# Sensor_Brushless_Driver_V1_0.net
KiCad netlist of a schematic drawn in Altium Designer
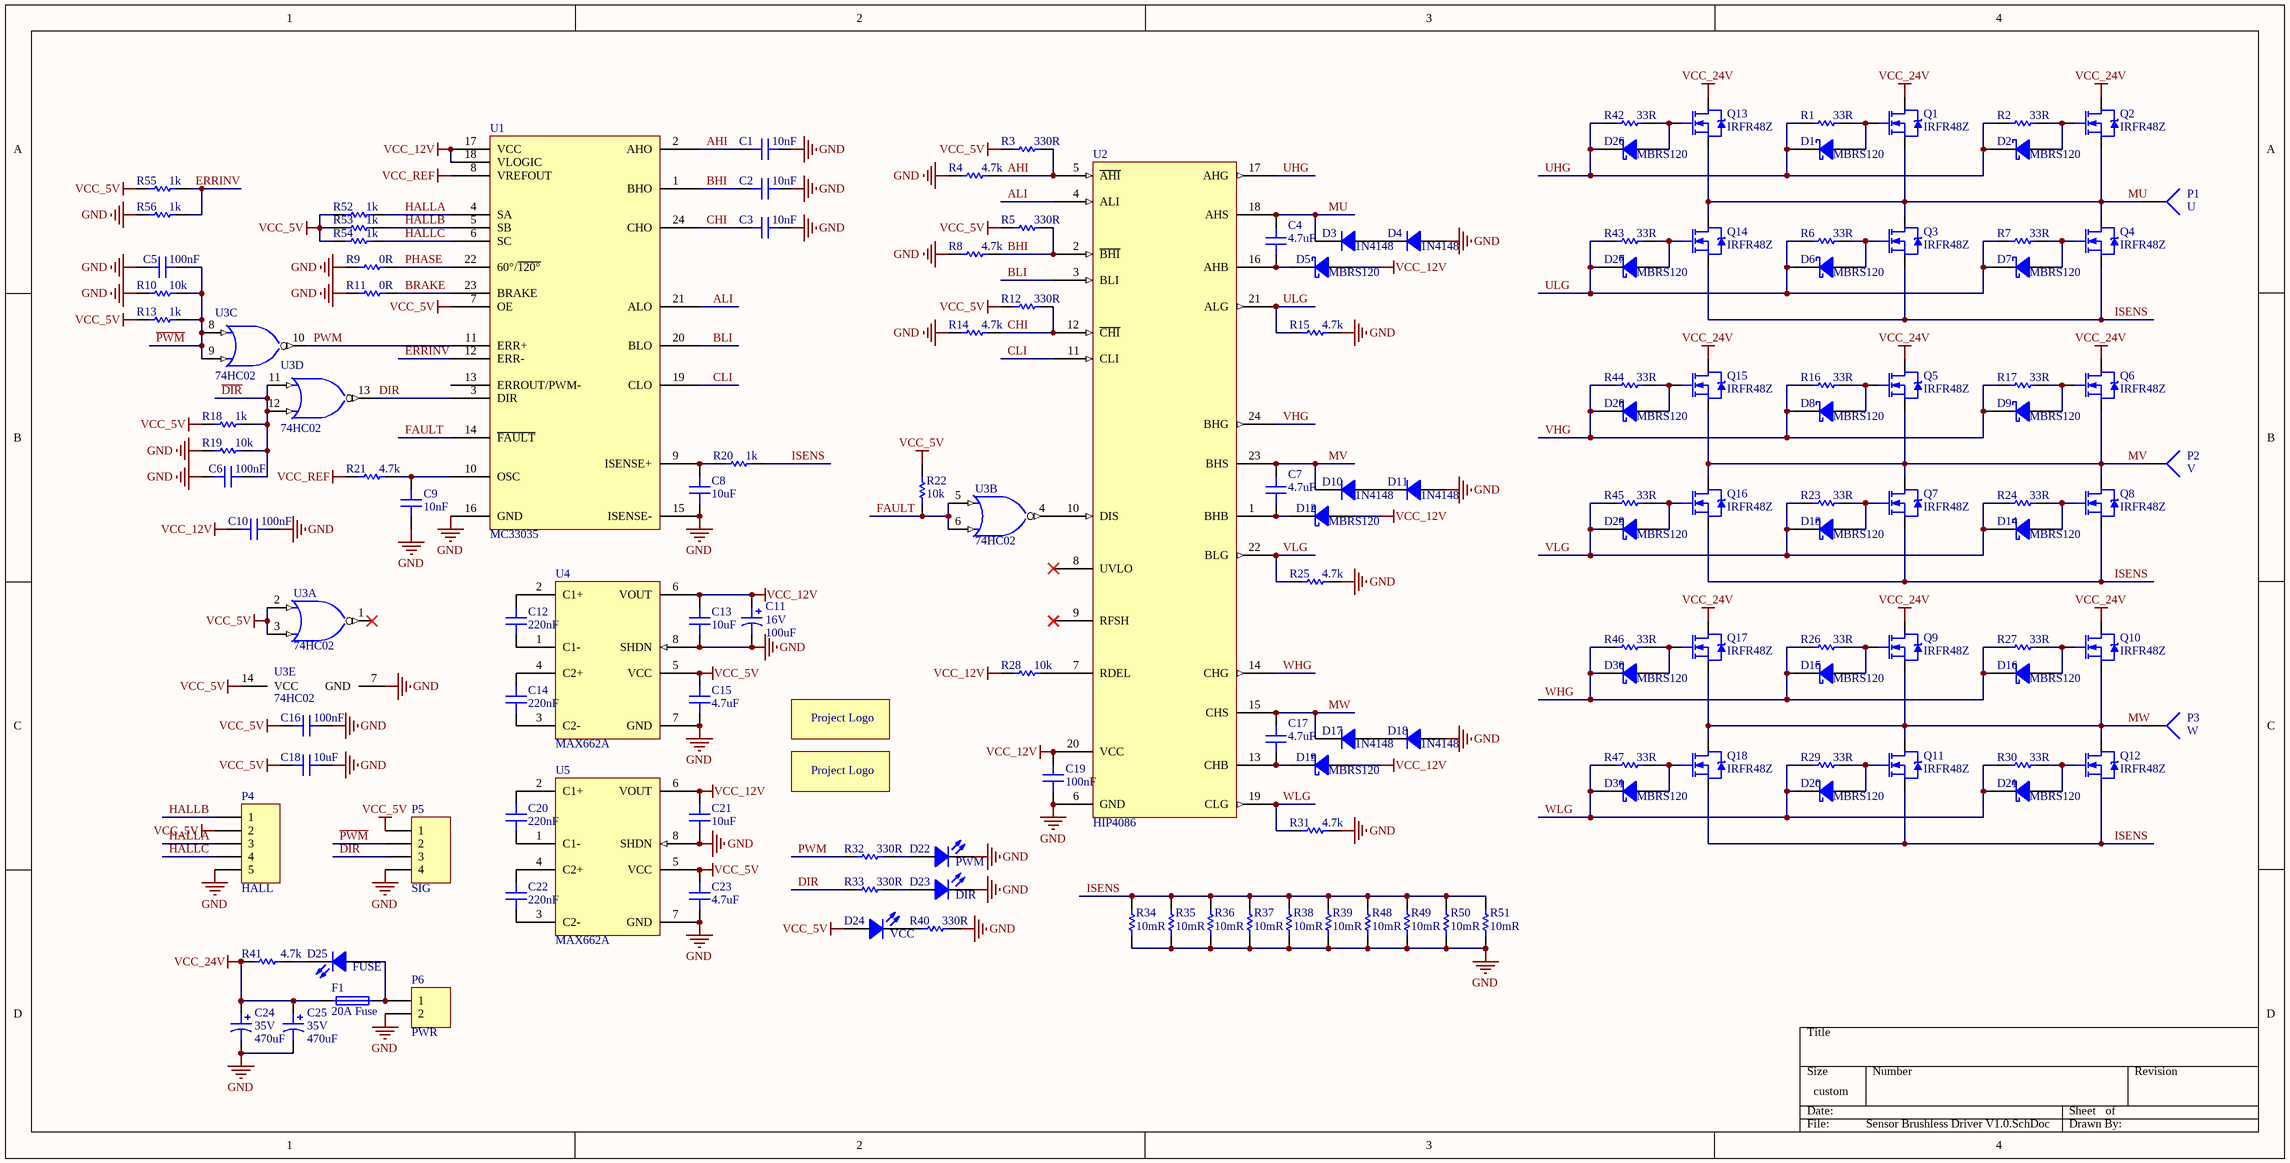
[diagram p0: Sensor Brushless Driver V1.0.SchDoc]

(export (version "E")
  (design (tool "Eeschema 10.0.6"))
  (components
    (comp (ref "C1")
      (value "10nF")
      (footprint "CC2012-0805")
      (description "Capacitor (Semiconductor SIM Model)")
      (libsource (lib "Robocon_RCL") (part "Cap Semi"))
    )
    (comp (ref "C2")
      (value "10nF")
      (footprint "CC2012-0805")
      (description "Capacitor (Semiconductor SIM Model)")
      (libsource (lib "Robocon_RCL") (part "Cap Semi"))
    )
    (comp (ref "C3")
      (value "10nF")
      (footprint "CC2012-0805")
      (description "Capacitor (Semiconductor SIM Model)")
      (libsource (lib "Robocon_RCL") (part "Cap Semi"))
    )
    (comp (ref "C4")
      (value "4.7uF")
      (footprint "CC2012-0805")
      (description "Capacitor (Semiconductor SIM Model)")
      (libsource (lib "Robocon_RCL") (part "Cap Semi"))
    )
    (comp (ref "C5")
      (value "100nF")
      (footprint "CC2012-0805")
      (description "Capacitor (Semiconductor SIM Model)")
      (libsource (lib "Robocon_RCL") (part "Cap Semi"))
    )
    (comp (ref "C6")
      (value "100nF")
      (footprint "CC2012-0805")
      (description "Capacitor (Semiconductor SIM Model)")
      (libsource (lib "Robocon_RCL") (part "Cap Semi"))
    )
    (comp (ref "C7")
      (value "4.7uF")
      (footprint "CC2012-0805")
      (description "Capacitor (Semiconductor SIM Model)")
      (libsource (lib "Robocon_RCL") (part "Cap Semi"))
    )
    (comp (ref "C8")
      (value "10uF")
      (footprint "CC3216-1206")
      (description "Capacitor (Semiconductor SIM Model)")
      (libsource (lib "Robocon_RCL") (part "Cap Semi"))
    )
    (comp (ref "C9")
      (value "10nF")
      (footprint "CC2012-0805")
      (description "Capacitor (Semiconductor SIM Model)")
      (libsource (lib "Robocon_RCL") (part "Cap Semi"))
    )
    (comp (ref "C10")
      (value "100nF")
      (footprint "CC2012-0805")
      (description "Capacitor (Semiconductor SIM Model)")
      (libsource (lib "Robocon_RCL") (part "Cap Semi"))
    )
    (comp (ref "C11")
      (value "100uF")
      (footprint "EIA7343")
      (description "Polarized Capacitor (Axial)")
      (fields (field (name "VOLTAGE") "16V"))
      (libsource (lib "Robocon_RCL") (part "Cap Pol SMD"))
    )
    (comp (ref "C12")
      (value "220nF")
      (footprint "CC2012-0805")
      (description "Capacitor (Semiconductor SIM Model)")
      (libsource (lib "Robocon_RCL") (part "Cap Semi"))
    )
    (comp (ref "C13")
      (value "10uF")
      (footprint "CC3216-1206")
      (description "Capacitor (Semiconductor SIM Model)")
      (libsource (lib "Robocon_RCL") (part "Cap Semi"))
    )
    (comp (ref "C14")
      (value "220nF")
      (footprint "CC2012-0805")
      (description "Capacitor (Semiconductor SIM Model)")
      (libsource (lib "Robocon_RCL") (part "Cap Semi"))
    )
    (comp (ref "C15")
      (value "4.7uF")
      (footprint "CC2012-0805")
      (description "Capacitor (Semiconductor SIM Model)")
      (libsource (lib "Robocon_RCL") (part "Cap Semi"))
    )
    (comp (ref "C16")
      (value "100nF")
      (footprint "CC2012-0805")
      (description "Capacitor (Semiconductor SIM Model)")
      (libsource (lib "Robocon_RCL") (part "Cap Semi"))
    )
    (comp (ref "C17")
      (value "4.7uF")
      (footprint "CC2012-0805")
      (description "Capacitor (Semiconductor SIM Model)")
      (libsource (lib "Robocon_RCL") (part "Cap Semi"))
    )
    (comp (ref "C18")
      (value "10uF")
      (footprint "CC3216-1206")
      (description "Capacitor (Semiconductor SIM Model)")
      (libsource (lib "Robocon_RCL") (part "Cap Semi"))
    )
    (comp (ref "C19")
      (value "100nF")
      (footprint "CC2012-0805")
      (description "Capacitor (Semiconductor SIM Model)")
      (libsource (lib "Robocon_RCL") (part "Cap Semi"))
    )
    (comp (ref "C20")
      (value "220nF")
      (footprint "CC2012-0805")
      (description "Capacitor (Semiconductor SIM Model)")
      (libsource (lib "Robocon_RCL") (part "Cap Semi"))
    )
    (comp (ref "C21")
      (value "10uF")
      (footprint "CC3216-1206")
      (description "Capacitor (Semiconductor SIM Model)")
      (libsource (lib "Robocon_RCL") (part "Cap Semi"))
    )
    (comp (ref "C22")
      (value "220nF")
      (footprint "CC2012-0805")
      (description "Capacitor (Semiconductor SIM Model)")
      (libsource (lib "Robocon_RCL") (part "Cap Semi"))
    )
    (comp (ref "C23")
      (value "4.7uF")
      (footprint "CC2012-0805")
      (description "Capacitor (Semiconductor SIM Model)")
      (libsource (lib "Robocon_RCL") (part "Cap Semi"))
    )
    (comp (ref "C24")
      (value "470uF")
      (footprint "CAP10x12")
      (description "Polarized Capacitor (Radial)")
      (fields (field (name "VOLTAGE") "35V"))
      (libsource (lib "Robocon_RCL") (part "Cap Pol DIP"))
    )
    (comp (ref "C25")
      (value "470uF")
      (footprint "CAP10x12")
      (description "Polarized Capacitor (Radial)")
      (fields (field (name "VOLTAGE") "35V"))
      (libsource (lib "Robocon_RCL") (part "Cap Pol DIP"))
    )
    (comp (ref "D1")
      (value "MBRS120")
      (footprint "SMA")
      (description "Schottky Diode")
      (libsource (lib "Robocon_BJT") (part "D Schottky"))
    )
    (comp (ref "D2")
      (value "MBRS120")
      (footprint "SMA")
      (description "Schottky Diode")
      (libsource (lib "Robocon_BJT") (part "D Schottky"))
    )
    (comp (ref "D3")
      (value "1N4148")
      (footprint "SOD-80")
      (description "General Purpose Diode")
      (libsource (lib "Robocon_BJT") (part "D General"))
    )
    (comp (ref "D4")
      (value "1N4148")
      (footprint "SOD-80")
      (description "General Purpose Diode")
      (libsource (lib "Robocon_BJT") (part "D General"))
    )
    (comp (ref "D5")
      (value "MBRS120")
      (footprint "SMA")
      (description "Schottky Diode")
      (libsource (lib "Robocon_BJT") (part "D Schottky"))
    )
    (comp (ref "D6")
      (value "MBRS120")
      (footprint "SMA")
      (description "Schottky Diode")
      (libsource (lib "Robocon_BJT") (part "D Schottky"))
    )
    (comp (ref "D7")
      (value "MBRS120")
      (footprint "SMA")
      (description "Schottky Diode")
      (libsource (lib "Robocon_BJT") (part "D Schottky"))
    )
    (comp (ref "D8")
      (value "MBRS120")
      (footprint "SMA")
      (description "Schottky Diode")
      (libsource (lib "Robocon_BJT") (part "D Schottky"))
    )
    (comp (ref "D9")
      (value "MBRS120")
      (footprint "SMA")
      (description "Schottky Diode")
      (libsource (lib "Robocon_BJT") (part "D Schottky"))
    )
    (comp (ref "D10")
      (value "1N4148")
      (footprint "SOD-80")
      (description "General Purpose Diode")
      (libsource (lib "Robocon_BJT") (part "D General"))
    )
    (comp (ref "D11")
      (value "1N4148")
      (footprint "SOD-80")
      (description "General Purpose Diode")
      (libsource (lib "Robocon_BJT") (part "D General"))
    )
    (comp (ref "D12")
      (value "MBRS120")
      (footprint "SMA")
      (description "Schottky Diode")
      (libsource (lib "Robocon_BJT") (part "D Schottky"))
    )
    (comp (ref "D13")
      (value "MBRS120")
      (footprint "SMA")
      (description "Schottky Diode")
      (libsource (lib "Robocon_BJT") (part "D Schottky"))
    )
    (comp (ref "D14")
      (value "MBRS120")
      (footprint "SMA")
      (description "Schottky Diode")
      (libsource (lib "Robocon_BJT") (part "D Schottky"))
    )
    (comp (ref "D15")
      (value "MBRS120")
      (footprint "SMA")
      (description "Schottky Diode")
      (libsource (lib "Robocon_BJT") (part "D Schottky"))
    )
    (comp (ref "D16")
      (value "MBRS120")
      (footprint "SMA")
      (description "Schottky Diode")
      (libsource (lib "Robocon_BJT") (part "D Schottky"))
    )
    (comp (ref "D17")
      (value "1N4148")
      (footprint "SOD-80")
      (description "General Purpose Diode")
      (libsource (lib "Robocon_BJT") (part "D General"))
    )
    (comp (ref "D18")
      (value "1N4148")
      (footprint "SOD-80")
      (description "General Purpose Diode")
      (libsource (lib "Robocon_BJT") (part "D General"))
    )
    (comp (ref "D19")
      (value "MBRS120")
      (footprint "SMA")
      (description "Schottky Diode")
      (libsource (lib "Robocon_BJT") (part "D Schottky"))
    )
    (comp (ref "D20")
      (value "MBRS120")
      (footprint "SMA")
      (description "Schottky Diode")
      (libsource (lib "Robocon_BJT") (part "D Schottky"))
    )
    (comp (ref "D21")
      (value "MBRS120")
      (footprint "SMA")
      (description "Schottky Diode")
      (libsource (lib "Robocon_BJT") (part "D Schottky"))
    )
    (comp (ref "D22")
      (value "PWM")
      (footprint "D0805")
      (description "Typical RED GaAs LED")
      (libsource (lib "Robocon_BJT") (part "LED"))
    )
    (comp (ref "D23")
      (value "DIR")
      (footprint "D0805")
      (description "Typical RED GaAs LED")
      (libsource (lib "Robocon_BJT") (part "LED"))
    )
    (comp (ref "D24")
      (value "VCC")
      (footprint "D0805")
      (description "Typical RED GaAs LED")
      (libsource (lib "Robocon_BJT") (part "LED"))
    )
    (comp (ref "D25")
      (value "FUSE")
      (footprint "D0805")
      (description "Typical RED GaAs LED")
      (libsource (lib "Robocon_BJT") (part "LED"))
    )
    (comp (ref "D26")
      (value "MBRS120")
      (footprint "SMA")
      (description "Schottky Diode")
      (libsource (lib "Robocon_BJT") (part "D Schottky"))
    )
    (comp (ref "D27")
      (value "MBRS120")
      (footprint "SMA")
      (description "Schottky Diode")
      (libsource (lib "Robocon_BJT") (part "D Schottky"))
    )
    (comp (ref "D28")
      (value "MBRS120")
      (footprint "SMA")
      (description "Schottky Diode")
      (libsource (lib "Robocon_BJT") (part "D Schottky"))
    )
    (comp (ref "D29")
      (value "MBRS120")
      (footprint "SMA")
      (description "Schottky Diode")
      (libsource (lib "Robocon_BJT") (part "D Schottky"))
    )
    (comp (ref "D30")
      (value "MBRS120")
      (footprint "SMA")
      (description "Schottky Diode")
      (libsource (lib "Robocon_BJT") (part "D Schottky"))
    )
    (comp (ref "D31")
      (value "MBRS120")
      (footprint "SMA")
      (description "Schottky Diode")
      (libsource (lib "Robocon_BJT") (part "D Schottky"))
    )
    (comp (ref "F1")
      (value "20A Fuse")
      (footprint "FUSE SOCKET")
      (description "Fuse")
      (libsource (lib "Robocon_RCL") (part "Fuse"))
    )
    (comp (ref "P1")
      (value "U")
      (footprint "2.5X4_WIRE_PAD")
      (description "Socket")
      (libsource (lib "Robocon_connectors") (part "Socket"))
    )
    (comp (ref "P2")
      (value "V")
      (footprint "2.5X4_WIRE_PAD")
      (description "Socket")
      (libsource (lib "Robocon_connectors") (part "Socket"))
    )
    (comp (ref "P3")
      (value "W")
      (footprint "2.5X4_WIRE_PAD")
      (description "Socket")
      (libsource (lib "Robocon_connectors") (part "Socket"))
    )
    (comp (ref "P4")
      (value "HALL")
      (footprint "LOCKEDHDR-5W")
      (description "Header, 5-Pin")
      (libsource (lib "Robocon_connectors") (part "Header 5"))
    )
    (comp (ref "P5")
      (value "SIG")
      (footprint "LOCKEDHDR-4W")
      (description "Header, 4-Pin")
      (libsource (lib "Robocon_connectors") (part "Header 4"))
    )
    (comp (ref "P6")
      (value "PWR")
      (footprint "T-CONNECTOR(M)")
      (description "Header, 2-Pin")
      (libsource (lib "Robocon_connectors") (part "Header 2"))
    )
    (comp (ref "Project1")
      (value "Project Logo")
      (footprint "Robocon_Logo")
      (libsource (lib "Robocon_RCL") (part "Project Logo"))
    )
    (comp (ref "Project2")
      (value "Project Logo")
      (footprint "Robocon_Logo")
      (libsource (lib "Robocon_RCL") (part "Project Logo"))
    )
    (comp (ref "Q1")
      (value "IRFR48Z")
      (footprint "TO-252AA")
      (description "HEXFET N-Channel Power MOSFET")
      (libsource (lib "Robocon_BJT") (part "IRFR48Z"))
    )
    (comp (ref "Q2")
      (value "IRFR48Z")
      (footprint "TO-252AA")
      (description "HEXFET N-Channel Power MOSFET")
      (libsource (lib "Robocon_BJT") (part "IRFR48Z"))
    )
    (comp (ref "Q3")
      (value "IRFR48Z")
      (footprint "TO-252AA")
      (description "HEXFET N-Channel Power MOSFET")
      (libsource (lib "Robocon_BJT") (part "IRFR48Z"))
    )
    (comp (ref "Q4")
      (value "IRFR48Z")
      (footprint "TO-252AA")
      (description "HEXFET N-Channel Power MOSFET")
      (libsource (lib "Robocon_BJT") (part "IRFR48Z"))
    )
    (comp (ref "Q5")
      (value "IRFR48Z")
      (footprint "TO-252AA")
      (description "HEXFET N-Channel Power MOSFET")
      (libsource (lib "Robocon_BJT") (part "IRFR48Z"))
    )
    (comp (ref "Q6")
      (value "IRFR48Z")
      (footprint "TO-252AA")
      (description "HEXFET N-Channel Power MOSFET")
      (libsource (lib "Robocon_BJT") (part "IRFR48Z"))
    )
    (comp (ref "Q7")
      (value "IRFR48Z")
      (footprint "TO-252AA")
      (description "HEXFET N-Channel Power MOSFET")
      (libsource (lib "Robocon_BJT") (part "IRFR48Z"))
    )
    (comp (ref "Q8")
      (value "IRFR48Z")
      (footprint "TO-252AA")
      (description "HEXFET N-Channel Power MOSFET")
      (libsource (lib "Robocon_BJT") (part "IRFR48Z"))
    )
    (comp (ref "Q9")
      (value "IRFR48Z")
      (footprint "TO-252AA")
      (description "HEXFET N-Channel Power MOSFET")
      (libsource (lib "Robocon_BJT") (part "IRFR48Z"))
    )
    (comp (ref "Q10")
      (value "IRFR48Z")
      (footprint "TO-252AA")
      (description "HEXFET N-Channel Power MOSFET")
      (libsource (lib "Robocon_BJT") (part "IRFR48Z"))
    )
    (comp (ref "Q11")
      (value "IRFR48Z")
      (footprint "TO-252AA")
      (description "HEXFET N-Channel Power MOSFET")
      (libsource (lib "Robocon_BJT") (part "IRFR48Z"))
    )
    (comp (ref "Q12")
      (value "IRFR48Z")
      (footprint "TO-252AA")
      (description "HEXFET N-Channel Power MOSFET")
      (libsource (lib "Robocon_BJT") (part "IRFR48Z"))
    )
    (comp (ref "Q13")
      (value "IRFR48Z")
      (footprint "TO-252AA")
      (description "HEXFET N-Channel Power MOSFET")
      (libsource (lib "Robocon_BJT") (part "IRFR48Z"))
    )
    (comp (ref "Q14")
      (value "IRFR48Z")
      (footprint "TO-252AA")
      (description "HEXFET N-Channel Power MOSFET")
      (libsource (lib "Robocon_BJT") (part "IRFR48Z"))
    )
    (comp (ref "Q15")
      (value "IRFR48Z")
      (footprint "TO-252AA")
      (description "HEXFET N-Channel Power MOSFET")
      (libsource (lib "Robocon_BJT") (part "IRFR48Z"))
    )
    (comp (ref "Q16")
      (value "IRFR48Z")
      (footprint "TO-252AA")
      (description "HEXFET N-Channel Power MOSFET")
      (libsource (lib "Robocon_BJT") (part "IRFR48Z"))
    )
    (comp (ref "Q17")
      (value "IRFR48Z")
      (footprint "TO-252AA")
      (description "HEXFET N-Channel Power MOSFET")
      (libsource (lib "Robocon_BJT") (part "IRFR48Z"))
    )
    (comp (ref "Q18")
      (value "IRFR48Z")
      (footprint "TO-252AA")
      (description "HEXFET N-Channel Power MOSFET")
      (libsource (lib "Robocon_BJT") (part "IRFR48Z"))
    )
    (comp (ref "R1")
      (value "33R")
      (footprint "CR2012-0805")
      (description "Semiconductor Resistor")
      (libsource (lib "Robocon_RCL") (part "Res Semi"))
    )
    (comp (ref "R2")
      (value "33R")
      (footprint "CR2012-0805")
      (description "Semiconductor Resistor")
      (libsource (lib "Robocon_RCL") (part "Res Semi"))
    )
    (comp (ref "R3")
      (value "330R")
      (footprint "CR2012-0805")
      (description "Semiconductor Resistor")
      (libsource (lib "Robocon_RCL") (part "Res Semi"))
    )
    (comp (ref "R4")
      (value "4.7k")
      (footprint "CR2012-0805")
      (description "Semiconductor Resistor")
      (libsource (lib "Robocon_RCL") (part "Res Semi"))
    )
    (comp (ref "R5")
      (value "330R")
      (footprint "CR2012-0805")
      (description "Semiconductor Resistor")
      (libsource (lib "Robocon_RCL") (part "Res Semi"))
    )
    (comp (ref "R6")
      (value "33R")
      (footprint "CR2012-0805")
      (description "Semiconductor Resistor")
      (libsource (lib "Robocon_RCL") (part "Res Semi"))
    )
    (comp (ref "R7")
      (value "33R")
      (footprint "CR2012-0805")
      (description "Semiconductor Resistor")
      (libsource (lib "Robocon_RCL") (part "Res Semi"))
    )
    (comp (ref "R8")
      (value "4.7k")
      (footprint "CR2012-0805")
      (description "Semiconductor Resistor")
      (libsource (lib "Robocon_RCL") (part "Res Semi"))
    )
    (comp (ref "R9")
      (value "0R")
      (footprint "CR2012-0805")
      (description "Semiconductor Resistor")
      (libsource (lib "Robocon_RCL") (part "Res Semi"))
    )
    (comp (ref "R10")
      (value "10k")
      (footprint "CR2012-0805")
      (description "Semiconductor Resistor")
      (libsource (lib "Robocon_RCL") (part "Res Semi"))
    )
    (comp (ref "R11")
      (value "0R")
      (footprint "CR2012-0805")
      (description "Semiconductor Resistor")
      (libsource (lib "Robocon_RCL") (part "Res Semi"))
    )
    (comp (ref "R12")
      (value "330R")
      (footprint "CR2012-0805")
      (description "Semiconductor Resistor")
      (libsource (lib "Robocon_RCL") (part "Res Semi"))
    )
    (comp (ref "R13")
      (value "1k")
      (footprint "CR2012-0805")
      (description "Semiconductor Resistor")
      (libsource (lib "Robocon_RCL") (part "Res Semi"))
    )
    (comp (ref "R14")
      (value "4.7k")
      (footprint "CR2012-0805")
      (description "Semiconductor Resistor")
      (libsource (lib "Robocon_RCL") (part "Res Semi"))
    )
    (comp (ref "R15")
      (value "4.7k")
      (footprint "CR2012-0805")
      (description "Semiconductor Resistor")
      (libsource (lib "Robocon_RCL") (part "Res Semi"))
    )
    (comp (ref "R16")
      (value "33R")
      (footprint "CR2012-0805")
      (description "Semiconductor Resistor")
      (libsource (lib "Robocon_RCL") (part "Res Semi"))
    )
    (comp (ref "R17")
      (value "33R")
      (footprint "CR2012-0805")
      (description "Semiconductor Resistor")
      (libsource (lib "Robocon_RCL") (part "Res Semi"))
    )
    (comp (ref "R18")
      (value "1k")
      (footprint "CR2012-0805")
      (description "Semiconductor Resistor")
      (libsource (lib "Robocon_RCL") (part "Res Semi"))
    )
    (comp (ref "R19")
      (value "10k")
      (footprint "CR2012-0805")
      (description "Semiconductor Resistor")
      (libsource (lib "Robocon_RCL") (part "Res Semi"))
    )
    (comp (ref "R20")
      (value "1k")
      (footprint "CR2012-0805")
      (description "Semiconductor Resistor")
      (libsource (lib "Robocon_RCL") (part "Res Semi"))
    )
    (comp (ref "R21")
      (value "4.7k")
      (footprint "CR2012-0805")
      (description "Semiconductor Resistor")
      (libsource (lib "Robocon_RCL") (part "Res Semi"))
    )
    (comp (ref "R22")
      (value "10k")
      (footprint "CR2012-0805")
      (description "Semiconductor Resistor")
      (libsource (lib "Robocon_RCL") (part "Res Semi"))
    )
    (comp (ref "R23")
      (value "33R")
      (footprint "CR2012-0805")
      (description "Semiconductor Resistor")
      (libsource (lib "Robocon_RCL") (part "Res Semi"))
    )
    (comp (ref "R24")
      (value "33R")
      (footprint "CR2012-0805")
      (description "Semiconductor Resistor")
      (libsource (lib "Robocon_RCL") (part "Res Semi"))
    )
    (comp (ref "R25")
      (value "4.7k")
      (footprint "CR2012-0805")
      (description "Semiconductor Resistor")
      (libsource (lib "Robocon_RCL") (part "Res Semi"))
    )
    (comp (ref "R26")
      (value "33R")
      (footprint "CR2012-0805")
      (description "Semiconductor Resistor")
      (libsource (lib "Robocon_RCL") (part "Res Semi"))
    )
    (comp (ref "R27")
      (value "33R")
      (footprint "CR2012-0805")
      (description "Semiconductor Resistor")
      (libsource (lib "Robocon_RCL") (part "Res Semi"))
    )
    (comp (ref "R28")
      (value "10k")
      (footprint "CR2012-0805")
      (description "Semiconductor Resistor")
      (libsource (lib "Robocon_RCL") (part "Res Semi"))
    )
    (comp (ref "R29")
      (value "33R")
      (footprint "CR2012-0805")
      (description "Semiconductor Resistor")
      (libsource (lib "Robocon_RCL") (part "Res Semi"))
    )
    (comp (ref "R30")
      (value "33R")
      (footprint "CR2012-0805")
      (description "Semiconductor Resistor")
      (libsource (lib "Robocon_RCL") (part "Res Semi"))
    )
    (comp (ref "R31")
      (value "4.7k")
      (footprint "CR2012-0805")
      (description "Semiconductor Resistor")
      (libsource (lib "Robocon_RCL") (part "Res Semi"))
    )
    (comp (ref "R32")
      (value "330R")
      (footprint "CR2012-0805")
      (description "Semiconductor Resistor")
      (libsource (lib "Robocon_RCL") (part "Res Semi"))
    )
    (comp (ref "R33")
      (value "330R")
      (footprint "CR2012-0805")
      (description "Semiconductor Resistor")
      (libsource (lib "Robocon_RCL") (part "Res Semi"))
    )
    (comp (ref "R34")
      (value "10mR")
      (footprint "CR6332-2512")
      (description "Semiconductor Resistor")
      (libsource (lib "Robocon_RCL") (part "Res Semi"))
    )
    (comp (ref "R35")
      (value "10mR")
      (footprint "CR6332-2512")
      (description "Semiconductor Resistor")
      (libsource (lib "Robocon_RCL") (part "Res Semi"))
    )
    (comp (ref "R36")
      (value "10mR")
      (footprint "CR6332-2512")
      (description "Semiconductor Resistor")
      (libsource (lib "Robocon_RCL") (part "Res Semi"))
    )
    (comp (ref "R37")
      (value "10mR")
      (footprint "CR6332-2512")
      (description "Semiconductor Resistor")
      (libsource (lib "Robocon_RCL") (part "Res Semi"))
    )
    (comp (ref "R38")
      (value "10mR")
      (footprint "CR6332-2512")
      (description "Semiconductor Resistor")
      (libsource (lib "Robocon_RCL") (part "Res Semi"))
    )
    (comp (ref "R39")
      (value "10mR")
      (footprint "CR6332-2512")
      (description "Semiconductor Resistor")
      (libsource (lib "Robocon_RCL") (part "Res Semi"))
    )
    (comp (ref "R40")
      (value "330R")
      (footprint "CR2012-0805")
      (description "Semiconductor Resistor")
      (libsource (lib "Robocon_RCL") (part "Res Semi"))
    )
    (comp (ref "R41")
      (value "4.7k")
      (footprint "CR2012-0805")
      (description "Semiconductor Resistor")
      (libsource (lib "Robocon_RCL") (part "Res Semi"))
    )
    (comp (ref "R42")
      (value "33R")
      (footprint "CR2012-0805")
      (description "Semiconductor Resistor")
      (libsource (lib "Robocon_RCL") (part "Res Semi"))
    )
    (comp (ref "R43")
      (value "33R")
      (footprint "CR2012-0805")
      (description "Semiconductor Resistor")
      (libsource (lib "Robocon_RCL") (part "Res Semi"))
    )
    (comp (ref "R44")
      (value "33R")
      (footprint "CR2012-0805")
      (description "Semiconductor Resistor")
      (libsource (lib "Robocon_RCL") (part "Res Semi"))
    )
    (comp (ref "R45")
      (value "33R")
      (footprint "CR2012-0805")
      (description "Semiconductor Resistor")
      (libsource (lib "Robocon_RCL") (part "Res Semi"))
    )
    (comp (ref "R46")
      (value "33R")
      (footprint "CR2012-0805")
      (description "Semiconductor Resistor")
      (libsource (lib "Robocon_RCL") (part "Res Semi"))
    )
    (comp (ref "R47")
      (value "33R")
      (footprint "CR2012-0805")
      (description "Semiconductor Resistor")
      (libsource (lib "Robocon_RCL") (part "Res Semi"))
    )
    (comp (ref "R48")
      (value "10mR")
      (footprint "CR6332-2512")
      (description "Semiconductor Resistor")
      (libsource (lib "Robocon_RCL") (part "Res Semi"))
    )
    (comp (ref "R49")
      (value "10mR")
      (footprint "CR6332-2512")
      (description "Semiconductor Resistor")
      (libsource (lib "Robocon_RCL") (part "Res Semi"))
    )
    (comp (ref "R50")
      (value "10mR")
      (footprint "CR6332-2512")
      (description "Semiconductor Resistor")
      (libsource (lib "Robocon_RCL") (part "Res Semi"))
    )
    (comp (ref "R51")
      (value "10mR")
      (footprint "CR6332-2512")
      (description "Semiconductor Resistor")
      (libsource (lib "Robocon_RCL") (part "Res Semi"))
    )
    (comp (ref "R52")
      (value "1k")
      (footprint "CR2012-0805")
      (description "Semiconductor Resistor")
      (libsource (lib "Robocon_RCL") (part "Res Semi"))
    )
    (comp (ref "R53")
      (value "1k")
      (footprint "CR2012-0805")
      (description "Semiconductor Resistor")
      (libsource (lib "Robocon_RCL") (part "Res Semi"))
    )
    (comp (ref "R54")
      (value "1k")
      (footprint "CR2012-0805")
      (description "Semiconductor Resistor")
      (libsource (lib "Robocon_RCL") (part "Res Semi"))
    )
    (comp (ref "R55")
      (value "1k")
      (footprint "CR2012-0805")
      (description "Semiconductor Resistor")
      (libsource (lib "Robocon_RCL") (part "Res Semi"))
    )
    (comp (ref "R56")
      (value "1k")
      (footprint "CR2012-0805")
      (description "Semiconductor Resistor")
      (libsource (lib "Robocon_RCL") (part "Res Semi"))
    )
    (comp (ref "U1")
      (value "MC33035")
      (footprint "SOP-24")
      (description "80V/2.5A Peak, High Frequency Full\r\nBridge FET Driver")
      (libsource (lib "Robocon_IC") (part "MC33035"))
    )
    (comp (ref "U2")
      (value "HIP4086")
      (footprint "SOP-24")
      (description "80V, 500mA, 3-Phase MOSFET Driver80V, 500mA, 3-Phase MOSFET Driver")
      (libsource (lib "Robocon_IC") (part "HIP4086"))
    )
    (comp (ref "U3")
      (value "74HC02")
      (footprint "SOP-14")
      (description "Quadruple 2-Input Positive-NOR Gate")
      (libsource (lib "Robocon_IC") (part "74HC02"))
    )
    (comp (ref "U4")
      (value "MAX662A")
      (footprint "SOP-8")
      (description "5V to 12V Charge Pump")
      (libsource (lib "Robocon_IC") (part "MAX662A"))
    )
    (comp (ref "U5")
      (value "MAX662A")
      (footprint "SOP-8")
      (description "5V to 12V Charge Pump")
      (libsource (lib "Robocon_IC") (part "MAX662A"))
    )
  )
  (nets
    (net (code "1") (name "/AHI") (class "Default")
      (node (ref "C1") (pin "2") (pinfunction "2_2") (pintype "passive"))
      (node (ref "R3") (pin "1") (pinfunction "1_1") (pintype "passive"))
      (node (ref "R4") (pin "1") (pinfunction "1_1") (pintype "passive"))
      (node (ref "U1") (pin "2") (pinfunction "AHO_2") (pintype "passive"))
      (node (ref "U2") (pin "5") (pinfunction "~{AHI}_5") (pintype "input"))
    )
    (net (code "2") (name "/ALI") (class "Default")
      (node (ref "U1") (pin "21") (pinfunction "ALO_21") (pintype "passive"))
      (node (ref "U2") (pin "4") (pinfunction "ALI_4") (pintype "input"))
    )
    (net (code "3") (name "/BHI") (class "Default")
      (node (ref "C2") (pin "2") (pinfunction "2_2") (pintype "passive"))
      (node (ref "R5") (pin "1") (pinfunction "1_1") (pintype "passive"))
      (node (ref "R8") (pin "1") (pinfunction "1_1") (pintype "passive"))
      (node (ref "U1") (pin "1") (pinfunction "BHO_1") (pintype "passive"))
      (node (ref "U2") (pin "2") (pinfunction "~{BHI}_2") (pintype "input"))
    )
    (net (code "4") (name "/BLI") (class "Default")
      (node (ref "U1") (pin "20") (pinfunction "BLO_20") (pintype "passive"))
      (node (ref "U2") (pin "3") (pinfunction "BLI_3") (pintype "input"))
    )
    (net (code "5") (name "/BRAKE") (class "Default")
      (node (ref "R11") (pin "1") (pinfunction "1_1") (pintype "passive"))
      (node (ref "U1") (pin "23") (pinfunction "BRAKE_23") (pintype "passive"))
    )
    (net (code "6") (name "/CHI") (class "Default")
      (node (ref "C3") (pin "2") (pinfunction "2_2") (pintype "passive"))
      (node (ref "R12") (pin "1") (pinfunction "1_1") (pintype "passive"))
      (node (ref "R14") (pin "1") (pinfunction "1_1") (pintype "passive"))
      (node (ref "U1") (pin "24") (pinfunction "CHO_24") (pintype "passive"))
      (node (ref "U2") (pin "12") (pinfunction "~{CHI}_12") (pintype "input"))
    )
    (net (code "7") (name "/CLI") (class "Default")
      (node (ref "U1") (pin "19") (pinfunction "CLO_19") (pintype "passive"))
      (node (ref "U2") (pin "11") (pinfunction "CLI_11") (pintype "input"))
    )
    (net (code "8") (name "/DIR") (class "Default")
      (node (ref "R33") (pin "2") (pinfunction "2_2") (pintype "passive"))
      (node (ref "U1") (pin "3") (pinfunction "DIR_3") (pintype "passive"))
      (node (ref "U3") (pin "13") (pinfunction "4Y_13") (pintype "output"))
    )
    (net (code "9") (name "/ERRINV") (class "Default")
      (node (ref "R55") (pin "1") (pinfunction "1_1") (pintype "passive"))
      (node (ref "R56") (pin "1") (pinfunction "1_1") (pintype "passive"))
      (node (ref "U1") (pin "12") (pinfunction "ERR-_12") (pintype "passive"))
    )
    (net (code "10") (name "/FAULT") (class "Default")
      (node (ref "R22") (pin "1") (pinfunction "1_1") (pintype "passive"))
      (node (ref "U1") (pin "14") (pinfunction "~{FAULT}_14") (pintype "passive"))
      (node (ref "U3") (pin "5") (pinfunction "2A_5") (pintype "input"))
      (node (ref "U3") (pin "6") (pinfunction "2B_6") (pintype "input"))
    )
    (net (code "11") (name "/HALLA") (class "Default")
      (node (ref "P4") (pin "3") (pinfunction "3_3") (pintype "passive"))
      (node (ref "R52") (pin "1") (pinfunction "1_1") (pintype "passive"))
      (node (ref "U1") (pin "4") (pinfunction "SA_4") (pintype "passive"))
    )
    (net (code "12") (name "/HALLB") (class "Default")
      (node (ref "P4") (pin "1") (pinfunction "1_1") (pintype "passive"))
      (node (ref "R53") (pin "1") (pinfunction "1_1") (pintype "passive"))
      (node (ref "U1") (pin "5") (pinfunction "SB_5") (pintype "passive"))
    )
    (net (code "13") (name "/HALLC") (class "Default")
      (node (ref "P4") (pin "4") (pinfunction "4_4") (pintype "passive"))
      (node (ref "R54") (pin "1") (pinfunction "1_1") (pintype "passive"))
      (node (ref "U1") (pin "6") (pinfunction "SC_6") (pintype "passive"))
    )
    (net (code "14") (name "/ISENS") (class "Default")
      (node (ref "Q11") (pin "3") (pinfunction "S_3") (pintype "passive"))
      (node (ref "Q12") (pin "3") (pinfunction "S_3") (pintype "passive"))
      (node (ref "Q14") (pin "3") (pinfunction "S_3") (pintype "passive"))
      (node (ref "Q16") (pin "3") (pinfunction "S_3") (pintype "passive"))
      (node (ref "Q18") (pin "3") (pinfunction "S_3") (pintype "passive"))
      (node (ref "Q3") (pin "3") (pinfunction "S_3") (pintype "passive"))
      (node (ref "Q4") (pin "3") (pinfunction "S_3") (pintype "passive"))
      (node (ref "Q7") (pin "3") (pinfunction "S_3") (pintype "passive"))
      (node (ref "Q8") (pin "3") (pinfunction "S_3") (pintype "passive"))
      (node (ref "R20") (pin "1") (pinfunction "1_1") (pintype "passive"))
      (node (ref "R34") (pin "2") (pinfunction "2_2") (pintype "passive"))
      (node (ref "R35") (pin "2") (pinfunction "2_2") (pintype "passive"))
      (node (ref "R36") (pin "2") (pinfunction "2_2") (pintype "passive"))
      (node (ref "R37") (pin "2") (pinfunction "2_2") (pintype "passive"))
      (node (ref "R38") (pin "2") (pinfunction "2_2") (pintype "passive"))
      (node (ref "R39") (pin "2") (pinfunction "2_2") (pintype "passive"))
      (node (ref "R48") (pin "2") (pinfunction "2_2") (pintype "passive"))
      (node (ref "R49") (pin "2") (pinfunction "2_2") (pintype "passive"))
      (node (ref "R50") (pin "2") (pinfunction "2_2") (pintype "passive"))
      (node (ref "R51") (pin "2") (pinfunction "2_2") (pintype "passive"))
    )
    (net (code "15") (name "/MU") (class "Default")
      (node (ref "C4") (pin "2") (pinfunction "2_2") (pintype "passive"))
      (node (ref "D3") (pin "2") (pinfunction "K_2") (pintype "passive"))
      (node (ref "P1") (pin "1") (pinfunction "1_1") (pintype "passive"))
      (node (ref "Q1") (pin "3") (pinfunction "S_3") (pintype "passive"))
      (node (ref "Q13") (pin "3") (pinfunction "S_3") (pintype "passive"))
      (node (ref "Q14") (pin "4") (pinfunction "D_4") (pintype "passive"))
      (node (ref "Q2") (pin "3") (pinfunction "S_3") (pintype "passive"))
      (node (ref "Q3") (pin "4") (pinfunction "D_4") (pintype "passive"))
      (node (ref "Q4") (pin "4") (pinfunction "D_4") (pintype "passive"))
      (node (ref "U2") (pin "18") (pinfunction "AHS_18") (pintype "passive"))
    )
    (net (code "16") (name "/MV") (class "Default")
      (node (ref "C7") (pin "2") (pinfunction "2_2") (pintype "passive"))
      (node (ref "D10") (pin "2") (pinfunction "K_2") (pintype "passive"))
      (node (ref "P2") (pin "1") (pinfunction "1_1") (pintype "passive"))
      (node (ref "Q15") (pin "3") (pinfunction "S_3") (pintype "passive"))
      (node (ref "Q16") (pin "4") (pinfunction "D_4") (pintype "passive"))
      (node (ref "Q5") (pin "3") (pinfunction "S_3") (pintype "passive"))
      (node (ref "Q6") (pin "3") (pinfunction "S_3") (pintype "passive"))
      (node (ref "Q7") (pin "4") (pinfunction "D_4") (pintype "passive"))
      (node (ref "Q8") (pin "4") (pinfunction "D_4") (pintype "passive"))
      (node (ref "U2") (pin "23") (pinfunction "BHS_23") (pintype "passive"))
    )
    (net (code "17") (name "/MW") (class "Default")
      (node (ref "C17") (pin "2") (pinfunction "2_2") (pintype "passive"))
      (node (ref "D17") (pin "2") (pinfunction "K_2") (pintype "passive"))
      (node (ref "P3") (pin "1") (pinfunction "1_1") (pintype "passive"))
      (node (ref "Q10") (pin "3") (pinfunction "S_3") (pintype "passive"))
      (node (ref "Q11") (pin "4") (pinfunction "D_4") (pintype "passive"))
      (node (ref "Q12") (pin "4") (pinfunction "D_4") (pintype "passive"))
      (node (ref "Q17") (pin "3") (pinfunction "S_3") (pintype "passive"))
      (node (ref "Q18") (pin "4") (pinfunction "D_4") (pintype "passive"))
      (node (ref "Q9") (pin "3") (pinfunction "S_3") (pintype "passive"))
      (node (ref "U2") (pin "15") (pinfunction "CHS_15") (pintype "passive"))
    )
    (net (code "18") (name "/PHASE") (class "Default")
      (node (ref "R9") (pin "1") (pinfunction "1_1") (pintype "passive"))
      (node (ref "U1") (pin "22") (pinfunction "60°/~{120°}_22") (pintype "passive"))
    )
    (net (code "19") (name "/PWM") (class "Default")
      (node (ref "R32") (pin "2") (pinfunction "2_2") (pintype "passive"))
      (node (ref "U1") (pin "11") (pinfunction "ERR+_11") (pintype "passive"))
      (node (ref "U3") (pin "10") (pinfunction "3Y_10") (pintype "output"))
    )
    (net (code "20") (name "/UHG") (class "Default")
      (node (ref "D1") (pin "2") (pinfunction "K_2") (pintype "passive"))
      (node (ref "D2") (pin "2") (pinfunction "K_2") (pintype "passive"))
      (node (ref "D26") (pin "2") (pinfunction "K_2") (pintype "passive"))
      (node (ref "R1") (pin "1") (pinfunction "1_1") (pintype "passive"))
      (node (ref "R2") (pin "1") (pinfunction "1_1") (pintype "passive"))
      (node (ref "R42") (pin "1") (pinfunction "1_1") (pintype "passive"))
      (node (ref "U2") (pin "17") (pinfunction "AHG_17") (pintype "output"))
    )
    (net (code "21") (name "/ULG") (class "Default")
      (node (ref "D27") (pin "2") (pinfunction "K_2") (pintype "passive"))
      (node (ref "D6") (pin "2") (pinfunction "K_2") (pintype "passive"))
      (node (ref "D7") (pin "2") (pinfunction "K_2") (pintype "passive"))
      (node (ref "R15") (pin "2") (pinfunction "2_2") (pintype "passive"))
      (node (ref "R43") (pin "1") (pinfunction "1_1") (pintype "passive"))
      (node (ref "R6") (pin "1") (pinfunction "1_1") (pintype "passive"))
      (node (ref "R7") (pin "1") (pinfunction "1_1") (pintype "passive"))
      (node (ref "U2") (pin "21") (pinfunction "ALG_21") (pintype "output"))
    )
    (net (code "22") (name "/VHG") (class "Default")
      (node (ref "D28") (pin "2") (pinfunction "K_2") (pintype "passive"))
      (node (ref "D8") (pin "2") (pinfunction "K_2") (pintype "passive"))
      (node (ref "D9") (pin "2") (pinfunction "K_2") (pintype "passive"))
      (node (ref "R16") (pin "1") (pinfunction "1_1") (pintype "passive"))
      (node (ref "R17") (pin "1") (pinfunction "1_1") (pintype "passive"))
      (node (ref "R44") (pin "1") (pinfunction "1_1") (pintype "passive"))
      (node (ref "U2") (pin "24") (pinfunction "BHG_24") (pintype "output"))
    )
    (net (code "23") (name "/VLG") (class "Default")
      (node (ref "D13") (pin "2") (pinfunction "K_2") (pintype "passive"))
      (node (ref "D14") (pin "2") (pinfunction "K_2") (pintype "passive"))
      (node (ref "D29") (pin "2") (pinfunction "K_2") (pintype "passive"))
      (node (ref "R23") (pin "1") (pinfunction "1_1") (pintype "passive"))
      (node (ref "R24") (pin "1") (pinfunction "1_1") (pintype "passive"))
      (node (ref "R25") (pin "2") (pinfunction "2_2") (pintype "passive"))
      (node (ref "R45") (pin "1") (pinfunction "1_1") (pintype "passive"))
      (node (ref "U2") (pin "22") (pinfunction "BLG_22") (pintype "output"))
    )
    (net (code "24") (name "/WHG") (class "Default")
      (node (ref "D15") (pin "2") (pinfunction "K_2") (pintype "passive"))
      (node (ref "D16") (pin "2") (pinfunction "K_2") (pintype "passive"))
      (node (ref "D30") (pin "2") (pinfunction "K_2") (pintype "passive"))
      (node (ref "R26") (pin "1") (pinfunction "1_1") (pintype "passive"))
      (node (ref "R27") (pin "1") (pinfunction "1_1") (pintype "passive"))
      (node (ref "R46") (pin "1") (pinfunction "1_1") (pintype "passive"))
      (node (ref "U2") (pin "14") (pinfunction "CHG_14") (pintype "output"))
    )
    (net (code "25") (name "/WLG") (class "Default")
      (node (ref "D20") (pin "2") (pinfunction "K_2") (pintype "passive"))
      (node (ref "D21") (pin "2") (pinfunction "K_2") (pintype "passive"))
      (node (ref "D31") (pin "2") (pinfunction "K_2") (pintype "passive"))
      (node (ref "R29") (pin "1") (pinfunction "1_1") (pintype "passive"))
      (node (ref "R30") (pin "1") (pinfunction "1_1") (pintype "passive"))
      (node (ref "R31") (pin "2") (pinfunction "2_2") (pintype "passive"))
      (node (ref "R47") (pin "1") (pinfunction "1_1") (pintype "passive"))
      (node (ref "U2") (pin "19") (pinfunction "CLG_19") (pintype "output"))
    )
    (net (code "26") (name "/~{DIR}") (class "Default")
      (node (ref "C6") (pin "1") (pinfunction "1_1") (pintype "passive"))
      (node (ref "P5") (pin "3") (pinfunction "3_3") (pintype "passive"))
      (node (ref "R18") (pin "1") (pinfunction "1_1") (pintype "passive"))
      (node (ref "R19") (pin "1") (pinfunction "1_1") (pintype "passive"))
      (node (ref "U3") (pin "11") (pinfunction "4A_11") (pintype "input"))
      (node (ref "U3") (pin "12") (pinfunction "4B_12") (pintype "input"))
    )
    (net (code "27") (name "/~{PWM}") (class "Default")
      (node (ref "C5") (pin "1") (pinfunction "1_1") (pintype "passive"))
      (node (ref "P5") (pin "2") (pinfunction "2_2") (pintype "passive"))
      (node (ref "R10") (pin "1") (pinfunction "1_1") (pintype "passive"))
      (node (ref "R13") (pin "1") (pinfunction "1_1") (pintype "passive"))
      (node (ref "U3") (pin "8") (pinfunction "3A_8") (pintype "input"))
      (node (ref "U3") (pin "9") (pinfunction "3B_9") (pintype "input"))
    )
    (net (code "28") (name "GND") (class "Default")
      (node (ref "C1") (pin "1") (pinfunction "1_1") (pintype "passive"))
      (node (ref "C10") (pin "2") (pinfunction "2_2") (pintype "passive"))
      (node (ref "C11") (pin "2") (pinfunction "2_2") (pintype "passive"))
      (node (ref "C13") (pin "2") (pinfunction "2_2") (pintype "passive"))
      (node (ref "C15") (pin "2") (pinfunction "2_2") (pintype "passive"))
      (node (ref "C16") (pin "2") (pinfunction "2_2") (pintype "passive"))
      (node (ref "C18") (pin "2") (pinfunction "2_2") (pintype "passive"))
      (node (ref "C19") (pin "2") (pinfunction "2_2") (pintype "passive"))
      (node (ref "C2") (pin "1") (pinfunction "1_1") (pintype "passive"))
      (node (ref "C21") (pin "2") (pinfunction "2_2") (pintype "passive"))
      (node (ref "C23") (pin "2") (pinfunction "2_2") (pintype "passive"))
      (node (ref "C24") (pin "2") (pinfunction "2_2") (pintype "passive"))
      (node (ref "C25") (pin "2") (pinfunction "2_2") (pintype "passive"))
      (node (ref "C3") (pin "1") (pinfunction "1_1") (pintype "passive"))
      (node (ref "C5") (pin "2") (pinfunction "2_2") (pintype "passive"))
      (node (ref "C6") (pin "2") (pinfunction "2_2") (pintype "passive"))
      (node (ref "C8") (pin "2") (pinfunction "2_2") (pintype "passive"))
      (node (ref "C9") (pin "2") (pinfunction "2_2") (pintype "passive"))
      (node (ref "D11") (pin "1") (pinfunction "A_1") (pintype "passive"))
      (node (ref "D18") (pin "1") (pinfunction "A_1") (pintype "passive"))
      (node (ref "D22") (pin "2") (pinfunction "K_2") (pintype "passive"))
      (node (ref "D23") (pin "2") (pinfunction "K_2") (pintype "passive"))
      (node (ref "D4") (pin "1") (pinfunction "A_1") (pintype "passive"))
      (node (ref "P4") (pin "5") (pinfunction "5_5") (pintype "passive"))
      (node (ref "P5") (pin "4") (pinfunction "4_4") (pintype "passive"))
      (node (ref "P6") (pin "2") (pinfunction "2_2") (pintype "passive"))
      (node (ref "R10") (pin "2") (pinfunction "2_2") (pintype "passive"))
      (node (ref "R11") (pin "2") (pinfunction "2_2") (pintype "passive"))
      (node (ref "R14") (pin "2") (pinfunction "2_2") (pintype "passive"))
      (node (ref "R15") (pin "1") (pinfunction "1_1") (pintype "passive"))
      (node (ref "R19") (pin "2") (pinfunction "2_2") (pintype "passive"))
      (node (ref "R25") (pin "1") (pinfunction "1_1") (pintype "passive"))
      (node (ref "R31") (pin "1") (pinfunction "1_1") (pintype "passive"))
      (node (ref "R34") (pin "1") (pinfunction "1_1") (pintype "passive"))
      (node (ref "R35") (pin "1") (pinfunction "1_1") (pintype "passive"))
      (node (ref "R36") (pin "1") (pinfunction "1_1") (pintype "passive"))
      (node (ref "R37") (pin "1") (pinfunction "1_1") (pintype "passive"))
      (node (ref "R38") (pin "1") (pinfunction "1_1") (pintype "passive"))
      (node (ref "R39") (pin "1") (pinfunction "1_1") (pintype "passive"))
      (node (ref "R4") (pin "2") (pinfunction "2_2") (pintype "passive"))
      (node (ref "R40") (pin "1") (pinfunction "1_1") (pintype "passive"))
      (node (ref "R48") (pin "1") (pinfunction "1_1") (pintype "passive"))
      (node (ref "R49") (pin "1") (pinfunction "1_1") (pintype "passive"))
      (node (ref "R50") (pin "1") (pinfunction "1_1") (pintype "passive"))
      (node (ref "R51") (pin "1") (pinfunction "1_1") (pintype "passive"))
      (node (ref "R56") (pin "2") (pinfunction "2_2") (pintype "passive"))
      (node (ref "R8") (pin "2") (pinfunction "2_2") (pintype "passive"))
      (node (ref "R9") (pin "2") (pinfunction "2_2") (pintype "passive"))
      (node (ref "U1") (pin "15") (pinfunction "ISENSE-_15") (pintype "passive"))
      (node (ref "U1") (pin "16") (pinfunction "GND_16") (pintype "passive"))
      (node (ref "U2") (pin "6") (pinfunction "GND_6") (pintype "passive"))
      (node (ref "U3") (pin "7") (pinfunction "GND_7") (pintype "power_in"))
      (node (ref "U4") (pin "7") (pinfunction "GND_7") (pintype "passive"))
      (node (ref "U4") (pin "8") (pinfunction "SHDN_8") (pintype "input"))
      (node (ref "U5") (pin "7") (pinfunction "GND_7") (pintype "passive"))
      (node (ref "U5") (pin "8") (pinfunction "SHDN_8") (pintype "input"))
    )
    (net (code "29") (name "Net-(D1-A)") (class "Default")
      (node (ref "D1") (pin "1") (pinfunction "A_1") (pintype "passive"))
      (node (ref "Q1") (pin "1") (pinfunction "G_1") (pintype "passive"))
      (node (ref "R1") (pin "2") (pinfunction "2_2") (pintype "passive"))
    )
    (net (code "30") (name "Net-(D2-A)") (class "Default")
      (node (ref "D2") (pin "1") (pinfunction "A_1") (pintype "passive"))
      (node (ref "Q2") (pin "1") (pinfunction "G_1") (pintype "passive"))
      (node (ref "R2") (pin "2") (pinfunction "2_2") (pintype "passive"))
    )
    (net (code "31") (name "Net-(D3-A)") (class "Default")
      (node (ref "D3") (pin "1") (pinfunction "A_1") (pintype "passive"))
      (node (ref "D4") (pin "2") (pinfunction "K_2") (pintype "passive"))
    )
    (net (code "32") (name "Net-(D5-K)") (class "Default")
      (node (ref "C4") (pin "1") (pinfunction "1_1") (pintype "passive"))
      (node (ref "D5") (pin "2") (pinfunction "K_2") (pintype "passive"))
      (node (ref "U2") (pin "16") (pinfunction "AHB_16") (pintype "passive"))
    )
    (net (code "33") (name "Net-(D6-A)") (class "Default")
      (node (ref "D6") (pin "1") (pinfunction "A_1") (pintype "passive"))
      (node (ref "Q3") (pin "1") (pinfunction "G_1") (pintype "passive"))
      (node (ref "R6") (pin "2") (pinfunction "2_2") (pintype "passive"))
    )
    (net (code "34") (name "Net-(D7-A)") (class "Default")
      (node (ref "D7") (pin "1") (pinfunction "A_1") (pintype "passive"))
      (node (ref "Q4") (pin "1") (pinfunction "G_1") (pintype "passive"))
      (node (ref "R7") (pin "2") (pinfunction "2_2") (pintype "passive"))
    )
    (net (code "35") (name "Net-(D8-A)") (class "Default")
      (node (ref "D8") (pin "1") (pinfunction "A_1") (pintype "passive"))
      (node (ref "Q5") (pin "1") (pinfunction "G_1") (pintype "passive"))
      (node (ref "R16") (pin "2") (pinfunction "2_2") (pintype "passive"))
    )
    (net (code "36") (name "Net-(D9-A)") (class "Default")
      (node (ref "D9") (pin "1") (pinfunction "A_1") (pintype "passive"))
      (node (ref "Q6") (pin "1") (pinfunction "G_1") (pintype "passive"))
      (node (ref "R17") (pin "2") (pinfunction "2_2") (pintype "passive"))
    )
    (net (code "37") (name "Net-(D10-A)") (class "Default")
      (node (ref "D10") (pin "1") (pinfunction "A_1") (pintype "passive"))
      (node (ref "D11") (pin "2") (pinfunction "K_2") (pintype "passive"))
    )
    (net (code "38") (name "Net-(D12-K)") (class "Default")
      (node (ref "C7") (pin "1") (pinfunction "1_1") (pintype "passive"))
      (node (ref "D12") (pin "2") (pinfunction "K_2") (pintype "passive"))
      (node (ref "U2") (pin "1") (pinfunction "BHB_1") (pintype "passive"))
    )
    (net (code "39") (name "Net-(D13-A)") (class "Default")
      (node (ref "D13") (pin "1") (pinfunction "A_1") (pintype "passive"))
      (node (ref "Q7") (pin "1") (pinfunction "G_1") (pintype "passive"))
      (node (ref "R23") (pin "2") (pinfunction "2_2") (pintype "passive"))
    )
    (net (code "40") (name "Net-(D14-A)") (class "Default")
      (node (ref "D14") (pin "1") (pinfunction "A_1") (pintype "passive"))
      (node (ref "Q8") (pin "1") (pinfunction "G_1") (pintype "passive"))
      (node (ref "R24") (pin "2") (pinfunction "2_2") (pintype "passive"))
    )
    (net (code "41") (name "Net-(D15-A)") (class "Default")
      (node (ref "D15") (pin "1") (pinfunction "A_1") (pintype "passive"))
      (node (ref "Q9") (pin "1") (pinfunction "G_1") (pintype "passive"))
      (node (ref "R26") (pin "2") (pinfunction "2_2") (pintype "passive"))
    )
    (net (code "42") (name "Net-(D16-A)") (class "Default")
      (node (ref "D16") (pin "1") (pinfunction "A_1") (pintype "passive"))
      (node (ref "Q10") (pin "1") (pinfunction "G_1") (pintype "passive"))
      (node (ref "R27") (pin "2") (pinfunction "2_2") (pintype "passive"))
    )
    (net (code "43") (name "Net-(D17-A)") (class "Default")
      (node (ref "D17") (pin "1") (pinfunction "A_1") (pintype "passive"))
      (node (ref "D18") (pin "2") (pinfunction "K_2") (pintype "passive"))
    )
    (net (code "44") (name "Net-(D19-K)") (class "Default")
      (node (ref "C17") (pin "1") (pinfunction "1_1") (pintype "passive"))
      (node (ref "D19") (pin "2") (pinfunction "K_2") (pintype "passive"))
      (node (ref "U2") (pin "13") (pinfunction "CHB_13") (pintype "passive"))
    )
    (net (code "45") (name "Net-(D20-A)") (class "Default")
      (node (ref "D20") (pin "1") (pinfunction "A_1") (pintype "passive"))
      (node (ref "Q11") (pin "1") (pinfunction "G_1") (pintype "passive"))
      (node (ref "R29") (pin "2") (pinfunction "2_2") (pintype "passive"))
    )
    (net (code "46") (name "Net-(D21-A)") (class "Default")
      (node (ref "D21") (pin "1") (pinfunction "A_1") (pintype "passive"))
      (node (ref "Q12") (pin "1") (pinfunction "G_1") (pintype "passive"))
      (node (ref "R30") (pin "2") (pinfunction "2_2") (pintype "passive"))
    )
    (net (code "47") (name "Net-(D22-A)") (class "Default")
      (node (ref "D22") (pin "1") (pinfunction "A_1") (pintype "passive"))
      (node (ref "R32") (pin "1") (pinfunction "1_1") (pintype "passive"))
    )
    (net (code "48") (name "Net-(D23-A)") (class "Default")
      (node (ref "D23") (pin "1") (pinfunction "A_1") (pintype "passive"))
      (node (ref "R33") (pin "1") (pinfunction "1_1") (pintype "passive"))
    )
    (net (code "49") (name "Net-(D24-K)") (class "Default")
      (node (ref "D24") (pin "2") (pinfunction "K_2") (pintype "passive"))
      (node (ref "R40") (pin "2") (pinfunction "2_2") (pintype "passive"))
    )
    (net (code "50") (name "Net-(D25-A)") (class "Default")
      (node (ref "D25") (pin "1") (pinfunction "A_1") (pintype "passive"))
      (node (ref "F1") (pin "2") (pinfunction "2_2") (pintype "passive"))
      (node (ref "P6") (pin "1") (pinfunction "1_1") (pintype "passive"))
    )
    (net (code "51") (name "Net-(D25-K)") (class "Default")
      (node (ref "D25") (pin "2") (pinfunction "K_2") (pintype "passive"))
      (node (ref "R41") (pin "2") (pinfunction "2_2") (pintype "passive"))
    )
    (net (code "52") (name "Net-(D26-A)") (class "Default")
      (node (ref "D26") (pin "1") (pinfunction "A_1") (pintype "passive"))
      (node (ref "Q13") (pin "1") (pinfunction "G_1") (pintype "passive"))
      (node (ref "R42") (pin "2") (pinfunction "2_2") (pintype "passive"))
    )
    (net (code "53") (name "Net-(D27-A)") (class "Default")
      (node (ref "D27") (pin "1") (pinfunction "A_1") (pintype "passive"))
      (node (ref "Q14") (pin "1") (pinfunction "G_1") (pintype "passive"))
      (node (ref "R43") (pin "2") (pinfunction "2_2") (pintype "passive"))
    )
    (net (code "54") (name "Net-(D28-A)") (class "Default")
      (node (ref "D28") (pin "1") (pinfunction "A_1") (pintype "passive"))
      (node (ref "Q15") (pin "1") (pinfunction "G_1") (pintype "passive"))
      (node (ref "R44") (pin "2") (pinfunction "2_2") (pintype "passive"))
    )
    (net (code "55") (name "Net-(D29-A)") (class "Default")
      (node (ref "D29") (pin "1") (pinfunction "A_1") (pintype "passive"))
      (node (ref "Q16") (pin "1") (pinfunction "G_1") (pintype "passive"))
      (node (ref "R45") (pin "2") (pinfunction "2_2") (pintype "passive"))
    )
    (net (code "56") (name "Net-(D30-A)") (class "Default")
      (node (ref "D30") (pin "1") (pinfunction "A_1") (pintype "passive"))
      (node (ref "Q17") (pin "1") (pinfunction "G_1") (pintype "passive"))
      (node (ref "R46") (pin "2") (pinfunction "2_2") (pintype "passive"))
    )
    (net (code "57") (name "Net-(D31-A)") (class "Default")
      (node (ref "D31") (pin "1") (pinfunction "A_1") (pintype "passive"))
      (node (ref "Q18") (pin "1") (pinfunction "G_1") (pintype "passive"))
      (node (ref "R47") (pin "2") (pinfunction "2_2") (pintype "passive"))
    )
    (net (code "58") (name "Net-(U1-ISENSE+)") (class "Default")
      (node (ref "C8") (pin "1") (pinfunction "1_1") (pintype "passive"))
      (node (ref "R20") (pin "2") (pinfunction "2_2") (pintype "passive"))
      (node (ref "U1") (pin "9") (pinfunction "ISENSE+_9") (pintype "passive"))
    )
    (net (code "59") (name "Net-(U1-OSC)") (class "Default")
      (node (ref "C9") (pin "1") (pinfunction "1_1") (pintype "passive"))
      (node (ref "R21") (pin "2") (pinfunction "2_2") (pintype "passive"))
      (node (ref "U1") (pin "10") (pinfunction "OSC_10") (pintype "passive"))
    )
    (net (code "60") (name "Net-(U2-DIS)") (class "Default")
      (node (ref "U2") (pin "10") (pinfunction "DIS_10") (pintype "input"))
      (node (ref "U3") (pin "4") (pinfunction "2Y_4") (pintype "output"))
    )
    (net (code "61") (name "Net-(U2-RDEL)") (class "Default")
      (node (ref "R28") (pin "1") (pinfunction "1_1") (pintype "passive"))
      (node (ref "U2") (pin "7") (pinfunction "RDEL_7") (pintype "passive"))
    )
    (net (code "62") (name "Net-(U4-C1+)") (class "Default")
      (node (ref "C12") (pin "2") (pinfunction "2_2") (pintype "passive"))
      (node (ref "U4") (pin "2") (pinfunction "C1+_2") (pintype "passive"))
    )
    (net (code "63") (name "Net-(U4-C1-)") (class "Default")
      (node (ref "C12") (pin "1") (pinfunction "1_1") (pintype "passive"))
      (node (ref "U4") (pin "1") (pinfunction "C1-_1") (pintype "passive"))
    )
    (net (code "64") (name "Net-(U4-C2+)") (class "Default")
      (node (ref "C14") (pin "2") (pinfunction "2_2") (pintype "passive"))
      (node (ref "U4") (pin "4") (pinfunction "C2+_4") (pintype "power_in"))
    )
    (net (code "65") (name "Net-(U4-C2-)") (class "Default")
      (node (ref "C14") (pin "1") (pinfunction "1_1") (pintype "passive"))
      (node (ref "U4") (pin "3") (pinfunction "C2-_3") (pintype "passive"))
    )
    (net (code "66") (name "Net-(U5-C1+)") (class "Default")
      (node (ref "C20") (pin "2") (pinfunction "2_2") (pintype "passive"))
      (node (ref "U5") (pin "2") (pinfunction "C1+_2") (pintype "passive"))
    )
    (net (code "67") (name "Net-(U5-C1-)") (class "Default")
      (node (ref "C20") (pin "1") (pinfunction "1_1") (pintype "passive"))
      (node (ref "U5") (pin "1") (pinfunction "C1-_1") (pintype "passive"))
    )
    (net (code "68") (name "Net-(U5-C2+)") (class "Default")
      (node (ref "C22") (pin "2") (pinfunction "2_2") (pintype "passive"))
      (node (ref "U5") (pin "4") (pinfunction "C2+_4") (pintype "power_in"))
    )
    (net (code "69") (name "Net-(U5-C2-)") (class "Default")
      (node (ref "C22") (pin "1") (pinfunction "1_1") (pintype "passive"))
      (node (ref "U5") (pin "3") (pinfunction "C2-_3") (pintype "passive"))
    )
    (net (code "70") (name "VCC_5V") (class "Default")
      (node (ref "C15") (pin "1") (pinfunction "1_1") (pintype "passive"))
      (node (ref "C16") (pin "1") (pinfunction "1_1") (pintype "passive"))
      (node (ref "C18") (pin "1") (pinfunction "1_1") (pintype "passive"))
      (node (ref "C23") (pin "1") (pinfunction "1_1") (pintype "passive"))
      (node (ref "D24") (pin "1") (pinfunction "A_1") (pintype "passive"))
      (node (ref "P4") (pin "2") (pinfunction "2_2") (pintype "passive"))
      (node (ref "P5") (pin "1") (pinfunction "1_1") (pintype "passive"))
      (node (ref "R12") (pin "2") (pinfunction "2_2") (pintype "passive"))
      (node (ref "R13") (pin "2") (pinfunction "2_2") (pintype "passive"))
      (node (ref "R18") (pin "2") (pinfunction "2_2") (pintype "passive"))
      (node (ref "R22") (pin "2") (pinfunction "2_2") (pintype "passive"))
      (node (ref "R3") (pin "2") (pinfunction "2_2") (pintype "passive"))
      (node (ref "R5") (pin "2") (pinfunction "2_2") (pintype "passive"))
      (node (ref "R52") (pin "2") (pinfunction "2_2") (pintype "passive"))
      (node (ref "R53") (pin "2") (pinfunction "2_2") (pintype "passive"))
      (node (ref "R54") (pin "2") (pinfunction "2_2") (pintype "passive"))
      (node (ref "R55") (pin "2") (pinfunction "2_2") (pintype "passive"))
      (node (ref "U1") (pin "7") (pinfunction "OE_7") (pintype "passive"))
      (node (ref "U3") (pin "14") (pinfunction "VCC_14") (pintype "power_in"))
      (node (ref "U3") (pin "2") (pinfunction "1A_2") (pintype "input"))
      (node (ref "U3") (pin "3") (pinfunction "1B_3") (pintype "input"))
      (node (ref "U4") (pin "5") (pinfunction "VCC_5") (pintype "passive"))
      (node (ref "U5") (pin "5") (pinfunction "VCC_5") (pintype "passive"))
    )
    (net (code "71") (name "VCC_12V") (class "Default")
      (node (ref "C10") (pin "1") (pinfunction "1_1") (pintype "passive"))
      (node (ref "C11") (pin "1") (pinfunction "1_1") (pintype "passive"))
      (node (ref "C13") (pin "1") (pinfunction "1_1") (pintype "passive"))
      (node (ref "C19") (pin "1") (pinfunction "1_1") (pintype "passive"))
      (node (ref "C21") (pin "1") (pinfunction "1_1") (pintype "passive"))
      (node (ref "D12") (pin "1") (pinfunction "A_1") (pintype "passive"))
      (node (ref "D19") (pin "1") (pinfunction "A_1") (pintype "passive"))
      (node (ref "D5") (pin "1") (pinfunction "A_1") (pintype "passive"))
      (node (ref "R28") (pin "2") (pinfunction "2_2") (pintype "passive"))
      (node (ref "U1") (pin "17") (pinfunction "VCC_17") (pintype "passive"))
      (node (ref "U1") (pin "18") (pinfunction "VLOGIC_18") (pintype "passive"))
      (node (ref "U2") (pin "20") (pinfunction "VCC_20") (pintype "passive"))
      (node (ref "U4") (pin "6") (pinfunction "VOUT_6") (pintype "passive"))
      (node (ref "U5") (pin "6") (pinfunction "VOUT_6") (pintype "passive"))
    )
    (net (code "72") (name "VCC_24V") (class "Default")
      (node (ref "C24") (pin "1") (pinfunction "1_1") (pintype "passive"))
      (node (ref "C25") (pin "1") (pinfunction "1_1") (pintype "passive"))
      (node (ref "F1") (pin "1") (pinfunction "1_1") (pintype "passive"))
      (node (ref "Q1") (pin "4") (pinfunction "D_4") (pintype "passive"))
      (node (ref "Q10") (pin "4") (pinfunction "D_4") (pintype "passive"))
      (node (ref "Q13") (pin "4") (pinfunction "D_4") (pintype "passive"))
      (node (ref "Q15") (pin "4") (pinfunction "D_4") (pintype "passive"))
      (node (ref "Q17") (pin "4") (pinfunction "D_4") (pintype "passive"))
      (node (ref "Q2") (pin "4") (pinfunction "D_4") (pintype "passive"))
      (node (ref "Q5") (pin "4") (pinfunction "D_4") (pintype "passive"))
      (node (ref "Q6") (pin "4") (pinfunction "D_4") (pintype "passive"))
      (node (ref "Q9") (pin "4") (pinfunction "D_4") (pintype "passive"))
      (node (ref "R41") (pin "1") (pinfunction "1_1") (pintype "passive"))
    )
    (net (code "73") (name "VCC_REF") (class "Default")
      (node (ref "R21") (pin "1") (pinfunction "1_1") (pintype "passive"))
      (node (ref "U1") (pin "8") (pinfunction "VREFOUT_8") (pintype "passive"))
    )
    (net (code "74") (name "unconnected-(U1-ERROUT{slash}PWM--Pad13)") (class "Default")
      (node (ref "U1") (pin "13") (pinfunction "ERROUT/PWM-_13") (pintype "passive"))
    )
    (net (code "75") (name "unconnected-(U2-RFSH-Pad9)") (class "Default")
      (node (ref "U2") (pin "9") (pinfunction "RFSH_9") (pintype "passive+no_connect"))
    )
    (net (code "76") (name "unconnected-(U2-UVLO-Pad8)") (class "Default")
      (node (ref "U2") (pin "8") (pinfunction "UVLO_8") (pintype "passive+no_connect"))
    )
    (net (code "77") (name "unconnected-(U3A-1Y-Pad1)") (class "Default")
      (node (ref "U3") (pin "1") (pinfunction "1Y_1") (pintype "output+no_connect"))
    )
  )
)
